# schematic_ap.net
KiCad netlist of a schematic drawn in EAGLE
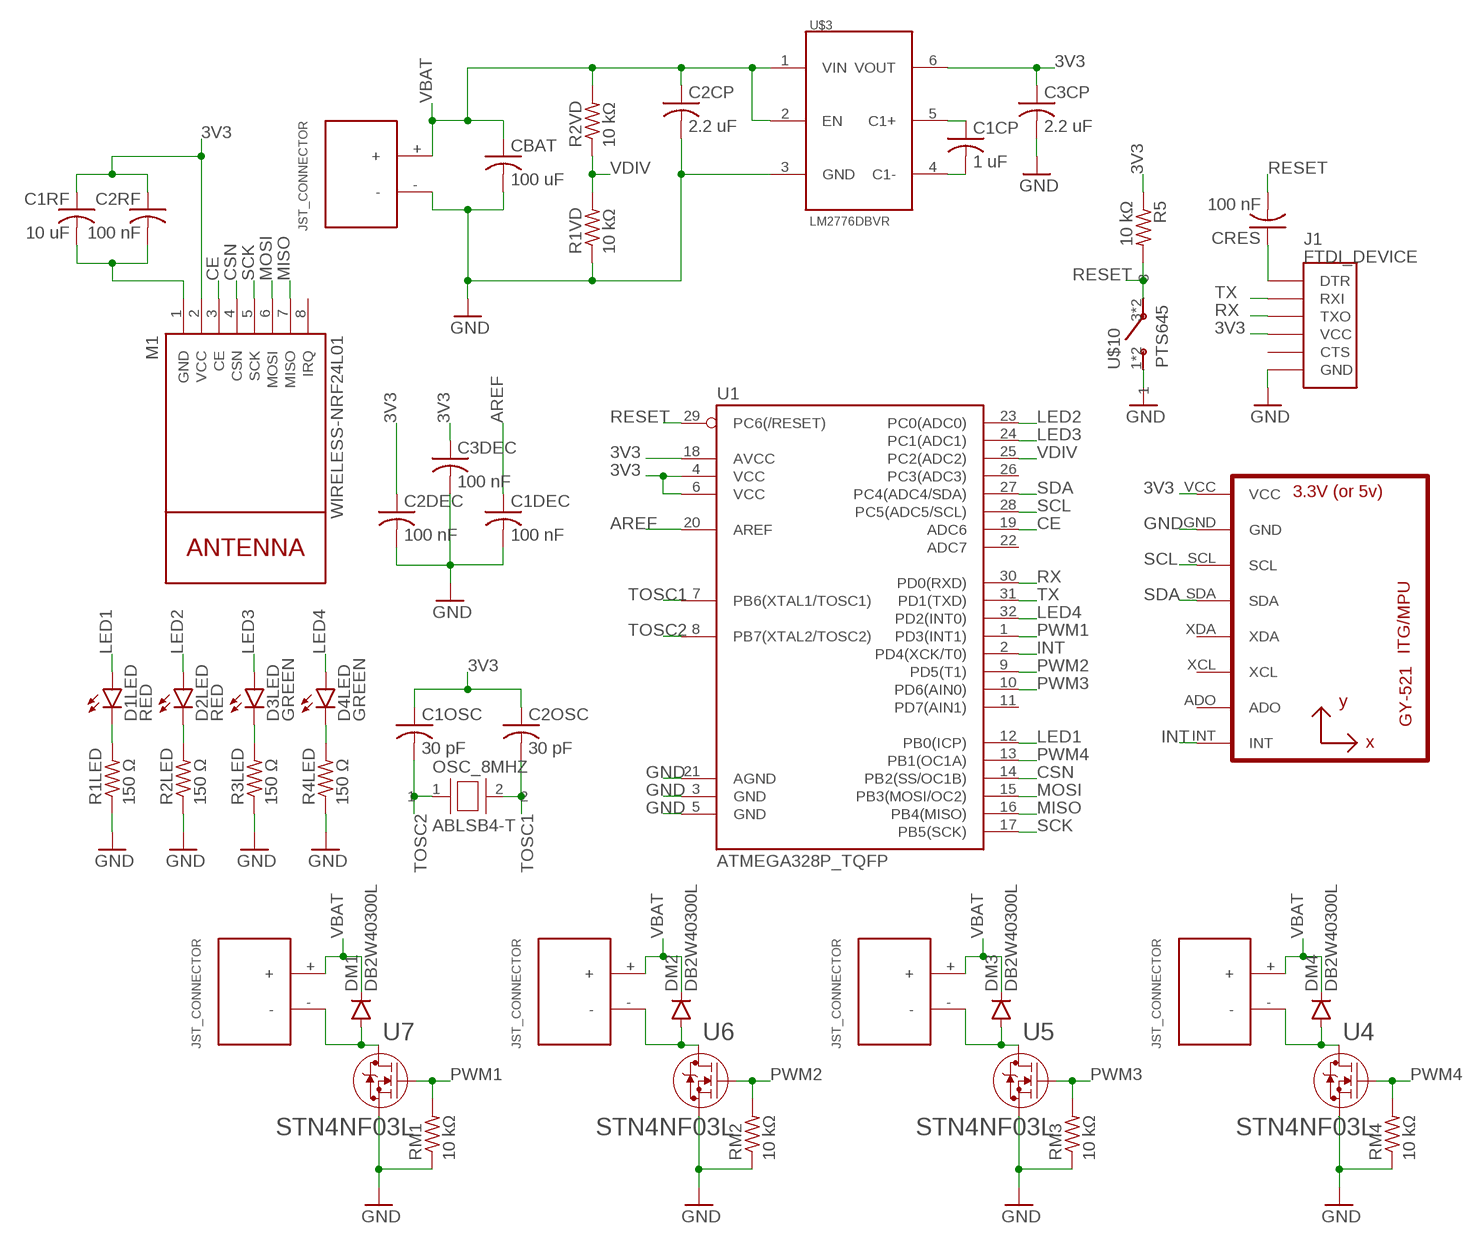
[diagram p0: schematic, sheet 1]

(export (version "E")
  (design (tool "Eeschema 10.0.6"))
  (components
    (comp (ref "C1CP")
      (value "1 uF")
      (footprint "eagle-import:C0603")
      (libsource (lib "eagle-import") (part "C-USC0603"))
    )
    (comp (ref "C1DEC")
      (value "100 nF")
      (footprint "eagle-import:C0603")
      (libsource (lib "eagle-import") (part "C-USC0603"))
    )
    (comp (ref "C1OSC")
      (value "30 pF")
      (footprint "eagle-import:C0603")
      (libsource (lib "eagle-import") (part "C-USC0603"))
    )
    (comp (ref "C1RF")
      (value "10 uF")
      (footprint "eagle-import:C0603")
      (libsource (lib "eagle-import") (part "C-USC0603"))
    )
    (comp (ref "C2CP")
      (value "2.2 uF")
      (footprint "eagle-import:C0603")
      (libsource (lib "eagle-import") (part "C-USC0603"))
    )
    (comp (ref "C2DEC")
      (value "100 nF")
      (footprint "eagle-import:C0603")
      (libsource (lib "eagle-import") (part "C-USC0603"))
    )
    (comp (ref "C2OSC")
      (value "30 pF")
      (footprint "eagle-import:C0603")
      (libsource (lib "eagle-import") (part "C-USC0603"))
    )
    (comp (ref "C2RF")
      (value "100 nF")
      (footprint "eagle-import:C0603")
      (libsource (lib "eagle-import") (part "C-USC0603"))
    )
    (comp (ref "C3CP")
      (value "2.2 uF")
      (footprint "eagle-import:C0603")
      (libsource (lib "eagle-import") (part "C-USC0603"))
    )
    (comp (ref "C3DEC")
      (value "100 nF")
      (footprint "eagle-import:C0603")
      (libsource (lib "eagle-import") (part "C-USC0603"))
    )
    (comp (ref "CBAT")
      (value "100 uF")
      (footprint "eagle-import:C0805")
      (libsource (lib "eagle-import") (part "C-USC0805"))
    )
    (comp (ref "CRES")
      (value "100 nF")
      (footprint "eagle-import:C0603")
      (libsource (lib "eagle-import") (part "C-USC0603"))
    )
    (comp (ref "D1LED")
      (value "RED")
      (footprint "eagle-import:LED-0603")
      (libsource (lib "eagle-import") (part "LED-RED0603"))
    )
    (comp (ref "D2LED")
      (value "RED")
      (footprint "eagle-import:LED-0603")
      (libsource (lib "eagle-import") (part "LED-RED0603"))
    )
    (comp (ref "D3LED")
      (value "GREEN")
      (footprint "eagle-import:LED-0603")
      (libsource (lib "eagle-import") (part "LED-GREEN0603"))
    )
    (comp (ref "D4LED")
      (value "GREEN")
      (footprint "eagle-import:LED-0603")
      (libsource (lib "eagle-import") (part "LED-GREEN0603"))
    )
    (comp (ref "DM1")
      (value "DB2W40300L")
      (footprint "eagle-import:MINI2-F3-B")
      (libsource (lib "eagle-import") (part "DB2W40300L"))
    )
    (comp (ref "DM2")
      (value "DB2W40300L")
      (footprint "eagle-import:MINI2-F3-B")
      (libsource (lib "eagle-import") (part "DB2W40300L"))
    )
    (comp (ref "DM3")
      (value "DB2W40300L")
      (footprint "eagle-import:MINI2-F3-B")
      (libsource (lib "eagle-import") (part "DB2W40300L"))
    )
    (comp (ref "DM4")
      (value "DB2W40300L")
      (footprint "eagle-import:MINI2-F3-B")
      (libsource (lib "eagle-import") (part "DB2W40300L"))
    )
    (comp (ref "J1")
      (value "FTDI_DEVICE")
      (footprint "eagle-import:FTDI_DEVICE_SIDE")
      (libsource (lib "eagle-import") (part "FTDI_DEVICE"))
    )
    (comp (ref "M1")
      (value "WIRELESS-NRF24L01")
      (footprint "eagle-import:WIRELESS-NRF24L01")
      (libsource (lib "eagle-import") (part "WIRELESS-NRF24L01"))
    )
    (comp (ref "OSC_8MHZ")
      (value "ABLSB4-T")
      (footprint "eagle-import:SOT-23")
      (libsource (lib "eagle-import") (part "ABLSB4-T"))
    )
    (comp (ref "R1LED")
      (value "150 Ω")
      (footprint "eagle-import:R0603")
      (libsource (lib "eagle-import") (part "R-US_R0603"))
    )
    (comp (ref "R1VD")
      (value "10 kΩ")
      (footprint "eagle-import:R0603")
      (libsource (lib "eagle-import") (part "R-US_R0603"))
    )
    (comp (ref "R2LED")
      (value "150 Ω")
      (footprint "eagle-import:R0603")
      (libsource (lib "eagle-import") (part "R-US_R0603"))
    )
    (comp (ref "R2VD")
      (value "10 kΩ")
      (footprint "eagle-import:R0603")
      (libsource (lib "eagle-import") (part "R-US_R0603"))
    )
    (comp (ref "R3LED")
      (value "150 Ω")
      (footprint "eagle-import:R0603")
      (libsource (lib "eagle-import") (part "R-US_R0603"))
    )
    (comp (ref "R4LED")
      (value "150 Ω")
      (footprint "eagle-import:R0603")
      (libsource (lib "eagle-import") (part "R-US_R0603"))
    )
    (comp (ref "R5")
      (value "10 kΩ")
      (footprint "eagle-import:R0603")
      (libsource (lib "eagle-import") (part "R-US_R0603"))
    )
    (comp (ref "RM1")
      (value "10 kΩ")
      (footprint "eagle-import:R0603")
      (libsource (lib "eagle-import") (part "R-US_R0603"))
    )
    (comp (ref "RM2")
      (value "10 kΩ")
      (footprint "eagle-import:R0603")
      (libsource (lib "eagle-import") (part "R-US_R0603"))
    )
    (comp (ref "RM3")
      (value "10 kΩ")
      (footprint "eagle-import:R0603")
      (libsource (lib "eagle-import") (part "R-US_R0603"))
    )
    (comp (ref "RM4")
      (value "10 kΩ")
      (footprint "eagle-import:R0603")
      (libsource (lib "eagle-import") (part "R-US_R0603"))
    )
    (comp (ref "U$3")
      (value "LM2776DBVR")
      (footprint "eagle-import:SOT23-5")
      (libsource (lib "eagle-import") (part "LM2776DBVR"))
    )
    (comp (ref "U$4")
      (value "JST_CONNECTOR_FEMALE")
      (footprint "eagle-import:JST_CONNECTOR_FEMALE")
      (libsource (lib "eagle-import") (part "JST_CONNECTOR_FEMALE"))
    )
    (comp (ref "U$5")
      (value "JST_CONNECTOR_FEMALE")
      (footprint "eagle-import:JST_CONNECTOR_FEMALE")
      (libsource (lib "eagle-import") (part "JST_CONNECTOR_FEMALE"))
    )
    (comp (ref "U$7")
      (value "JST_CONNECTOR_FEMALE")
      (footprint "eagle-import:JST_CONNECTOR_FEMALE")
      (libsource (lib "eagle-import") (part "JST_CONNECTOR_FEMALE"))
    )
    (comp (ref "U$9")
      (value "JST_CONNECTOR_FEMALE")
      (footprint "eagle-import:JST_CONNECTOR_FEMALE")
      (libsource (lib "eagle-import") (part "JST_CONNECTOR_FEMALE"))
    )
    (comp (ref "U$10")
      (value "PTS645")
      (footprint "eagle-import:SOT-35")
      (libsource (lib "eagle-import") (part "PTS645"))
    )
    (comp (ref "U$11")
      (value "JST_CONNECTOR_FEMALE")
      (footprint "eagle-import:JST_CONNECTOR_FEMALE")
      (libsource (lib "eagle-import") (part "JST_CONNECTOR_FEMALE"))
    )
    (comp (ref "U1")
      (value "ATMEGA328P_TQFP")
      (footprint "eagle-import:TQFP32-08")
      (libsource (lib "eagle-import") (part "ATMEGA328P_TQFP"))
    )
    (comp (ref "U2")
      (value "GY-521MPU6050")
      (footprint "eagle-import:GY-521")
      (libsource (lib "eagle-import") (part "GY-521MPU6050"))
    )
    (comp (ref "U4")
      (value "STN4NF03L")
      (footprint "eagle-import:SOT-223")
      (libsource (lib "eagle-import") (part "STN4NF03L"))
    )
    (comp (ref "U5")
      (value "STN4NF03L")
      (footprint "eagle-import:SOT-223")
      (libsource (lib "eagle-import") (part "STN4NF03L"))
    )
    (comp (ref "U6")
      (value "STN4NF03L")
      (footprint "eagle-import:SOT-223")
      (libsource (lib "eagle-import") (part "STN4NF03L"))
    )
    (comp (ref "U7")
      (value "STN4NF03L")
      (footprint "eagle-import:SOT-223")
      (libsource (lib "eagle-import") (part "STN4NF03L"))
    )
  )
  (nets
    (net (code "1") (name "/3V3") (class "Default")
      (node (ref "C1OSC") (pin "1") (pinfunction "1_1") (pintype "passive"))
      (node (ref "C1RF") (pin "1") (pinfunction "1_1") (pintype "passive"))
      (node (ref "C2DEC") (pin "1") (pinfunction "1_1") (pintype "passive"))
      (node (ref "C2OSC") (pin "1") (pinfunction "1_1") (pintype "passive"))
      (node (ref "C2RF") (pin "1") (pinfunction "1_1") (pintype "passive"))
      (node (ref "C3CP") (pin "1") (pinfunction "1_1") (pintype "passive"))
      (node (ref "C3DEC") (pin "1") (pinfunction "1_1") (pintype "passive"))
      (node (ref "J1") (pin "P$4") (pinfunction "VCC_P$4") (pintype "bidirectional"))
      (node (ref "M1") (pin "2") (pinfunction "VCC_2") (pintype "power_in"))
      (node (ref "R5") (pin "1") (pinfunction "1_1") (pintype "passive"))
      (node (ref "U$3") (pin "6") (pinfunction "VOUT_6") (pintype "bidirectional"))
      (node (ref "U1") (pin "18") (pinfunction "AVCC_18") (pintype "bidirectional"))
      (node (ref "U1") (pin "4") (pinfunction "VCC_4") (pintype "bidirectional"))
      (node (ref "U1") (pin "6") (pinfunction "VCC_6") (pintype "bidirectional"))
      (node (ref "U2") (pin "VCC") (pinfunction "VCC_VCC") (pintype "bidirectional"))
    )
    (net (code "2") (name "/AREF") (class "Default")
      (node (ref "C1DEC") (pin "1") (pinfunction "1_1") (pintype "passive"))
      (node (ref "U1") (pin "20") (pinfunction "AREF_20") (pintype "bidirectional"))
    )
    (net (code "3") (name "/CE") (class "Default")
      (node (ref "M1") (pin "3") (pinfunction "CE_3") (pintype "bidirectional"))
      (node (ref "U1") (pin "19") (pinfunction "ADC6_19") (pintype "bidirectional"))
    )
    (net (code "4") (name "/CSN") (class "Default")
      (node (ref "M1") (pin "4") (pinfunction "CSN_4") (pintype "bidirectional"))
      (node (ref "U1") (pin "14") (pinfunction "PB2(SS/OC1B)_14") (pintype "bidirectional"))
    )
    (net (code "5") (name "/INT") (class "Default")
      (node (ref "U1") (pin "2") (pinfunction "PD4(XCK/T0)_2") (pintype "bidirectional"))
      (node (ref "U2") (pin "INT") (pinfunction "INT_INT") (pintype "bidirectional"))
    )
    (net (code "6") (name "/LED1") (class "Default")
      (node (ref "D1LED") (pin "A") (pinfunction "A_A") (pintype "passive"))
      (node (ref "U1") (pin "12") (pinfunction "PB0(ICP)_12") (pintype "bidirectional"))
    )
    (net (code "7") (name "/LED2") (class "Default")
      (node (ref "D2LED") (pin "A") (pinfunction "A_A") (pintype "passive"))
      (node (ref "U1") (pin "23") (pinfunction "PC0(ADC0)_23") (pintype "bidirectional"))
    )
    (net (code "8") (name "/LED3") (class "Default")
      (node (ref "D3LED") (pin "A") (pinfunction "A_A") (pintype "passive"))
      (node (ref "U1") (pin "24") (pinfunction "PC1(ADC1)_24") (pintype "bidirectional"))
    )
    (net (code "9") (name "/LED4") (class "Default")
      (node (ref "D4LED") (pin "A") (pinfunction "A_A") (pintype "passive"))
      (node (ref "U1") (pin "32") (pinfunction "PD2(INT0)_32") (pintype "bidirectional"))
    )
    (net (code "10") (name "/MISO") (class "Default")
      (node (ref "M1") (pin "7") (pinfunction "MISO_7") (pintype "bidirectional"))
      (node (ref "U1") (pin "16") (pinfunction "PB4(MISO)_16") (pintype "bidirectional"))
    )
    (net (code "11") (name "/MOSI") (class "Default")
      (node (ref "M1") (pin "6") (pinfunction "MOSI_6") (pintype "bidirectional"))
      (node (ref "U1") (pin "15") (pinfunction "PB3(MOSI/OC2)_15") (pintype "bidirectional"))
    )
    (net (code "12") (name "/PWM1") (class "Default")
      (node (ref "RM1") (pin "2") (pinfunction "2_2") (pintype "passive"))
      (node (ref "U1") (pin "1") (pinfunction "PD3(INT1)_1") (pintype "bidirectional"))
      (node (ref "U7") (pin "1") (pinfunction "1_1") (pintype "passive"))
    )
    (net (code "13") (name "/PWM2") (class "Default")
      (node (ref "RM2") (pin "2") (pinfunction "2_2") (pintype "passive"))
      (node (ref "U1") (pin "9") (pinfunction "PD5(T1)_9") (pintype "bidirectional"))
      (node (ref "U6") (pin "1") (pinfunction "1_1") (pintype "passive"))
    )
    (net (code "14") (name "/PWM3") (class "Default")
      (node (ref "RM3") (pin "2") (pinfunction "2_2") (pintype "passive"))
      (node (ref "U1") (pin "10") (pinfunction "PD6(AIN0)_10") (pintype "bidirectional"))
      (node (ref "U5") (pin "1") (pinfunction "1_1") (pintype "passive"))
    )
    (net (code "15") (name "/PWM4") (class "Default")
      (node (ref "RM4") (pin "2") (pinfunction "2_2") (pintype "passive"))
      (node (ref "U1") (pin "13") (pinfunction "PB1(OC1A)_13") (pintype "bidirectional"))
      (node (ref "U4") (pin "1") (pinfunction "1_1") (pintype "passive"))
    )
    (net (code "16") (name "/RESET") (class "Default")
      (node (ref "CRES") (pin "2") (pinfunction "2_2") (pintype "passive"))
      (node (ref "R5") (pin "2") (pinfunction "2_2") (pintype "passive"))
      (node (ref "U$10") (pin "3") (pinfunction "3_3") (pintype "bidirectional"))
      (node (ref "U$10") (pin "4") (pinfunction "3_4") (pintype "bidirectional"))
      (node (ref "U1") (pin "29") (pinfunction "PC6(/RESET)_29") (pintype "bidirectional"))
    )
    (net (code "17") (name "/RX") (class "Default")
      (node (ref "J1") (pin "P$3") (pinfunction "TXO_P$3") (pintype "bidirectional"))
      (node (ref "U1") (pin "30") (pinfunction "PD0(RXD)_30") (pintype "bidirectional"))
    )
    (net (code "18") (name "/SCK") (class "Default")
      (node (ref "M1") (pin "5") (pinfunction "SCK_5") (pintype "bidirectional"))
      (node (ref "U1") (pin "17") (pinfunction "PB5(SCK)_17") (pintype "bidirectional"))
    )
    (net (code "19") (name "/SCL") (class "Default")
      (node (ref "U1") (pin "28") (pinfunction "PC5(ADC5/SCL)_28") (pintype "bidirectional"))
      (node (ref "U2") (pin "SCL") (pinfunction "SCL_SCL") (pintype "bidirectional"))
    )
    (net (code "20") (name "/SDA") (class "Default")
      (node (ref "U1") (pin "27") (pinfunction "PC4(ADC4/SDA)_27") (pintype "bidirectional"))
      (node (ref "U2") (pin "SDA") (pinfunction "SDA_SDA") (pintype "bidirectional"))
    )
    (net (code "21") (name "/TOSC1") (class "Default")
      (node (ref "C2OSC") (pin "2") (pinfunction "2_2") (pintype "passive"))
      (node (ref "OSC_8MHZ") (pin "2") (pinfunction "2_2") (pintype "bidirectional"))
      (node (ref "U1") (pin "7") (pinfunction "PB6(XTAL1/TOSC1)_7") (pintype "bidirectional"))
    )
    (net (code "22") (name "/TOSC2") (class "Default")
      (node (ref "C1OSC") (pin "2") (pinfunction "2_2") (pintype "passive"))
      (node (ref "OSC_8MHZ") (pin "1") (pinfunction "1_1") (pintype "bidirectional"))
      (node (ref "U1") (pin "8") (pinfunction "PB7(XTAL2/TOSC2)_8") (pintype "bidirectional"))
    )
    (net (code "23") (name "/TX") (class "Default")
      (node (ref "J1") (pin "P$2") (pinfunction "RXI_P$2") (pintype "bidirectional"))
      (node (ref "U1") (pin "31") (pinfunction "PD1(TXD)_31") (pintype "bidirectional"))
    )
    (net (code "24") (name "/VBAT") (class "Default")
      (node (ref "C2CP") (pin "1") (pinfunction "1_1") (pintype "passive"))
      (node (ref "CBAT") (pin "1") (pinfunction "1_1") (pintype "passive"))
      (node (ref "DM1") (pin "NEG") (pinfunction "GPIN_NEG") (pintype "passive"))
      (node (ref "DM2") (pin "NEG") (pinfunction "GPIN_NEG") (pintype "passive"))
      (node (ref "DM3") (pin "NEG") (pinfunction "GPIN_NEG") (pintype "passive"))
      (node (ref "DM4") (pin "NEG") (pinfunction "GPIN_NEG") (pintype "passive"))
      (node (ref "R2VD") (pin "2") (pinfunction "2_2") (pintype "passive"))
      (node (ref "U$11") (pin "+") (pinfunction "+_+") (pintype "bidirectional"))
      (node (ref "U$3") (pin "1") (pinfunction "VIN_1") (pintype "bidirectional"))
      (node (ref "U$3") (pin "2") (pinfunction "EN_2") (pintype "bidirectional"))
      (node (ref "U$4") (pin "+") (pinfunction "+_+") (pintype "bidirectional"))
      (node (ref "U$5") (pin "+") (pinfunction "+_+") (pintype "bidirectional"))
      (node (ref "U$7") (pin "+") (pinfunction "+_+") (pintype "bidirectional"))
      (node (ref "U$9") (pin "+") (pinfunction "+_+") (pintype "bidirectional"))
    )
    (net (code "25") (name "/VDIV") (class "Default")
      (node (ref "R1VD") (pin "2") (pinfunction "2_2") (pintype "passive"))
      (node (ref "R2VD") (pin "1") (pinfunction "1_1") (pintype "passive"))
      (node (ref "U1") (pin "25") (pinfunction "PC2(ADC2)_25") (pintype "bidirectional"))
    )
    (net (code "26") (name "GND") (class "Default")
      (node (ref "C1DEC") (pin "2") (pinfunction "2_2") (pintype "passive"))
      (node (ref "C2CP") (pin "2") (pinfunction "2_2") (pintype "passive"))
      (node (ref "C2DEC") (pin "2") (pinfunction "2_2") (pintype "passive"))
      (node (ref "C3CP") (pin "2") (pinfunction "2_2") (pintype "passive"))
      (node (ref "C3DEC") (pin "2") (pinfunction "2_2") (pintype "passive"))
      (node (ref "CBAT") (pin "2") (pinfunction "2_2") (pintype "passive"))
      (node (ref "J1") (pin "P$6") (pinfunction "GND_P$6") (pintype "bidirectional"))
      (node (ref "R1LED") (pin "1") (pinfunction "1_1") (pintype "passive"))
      (node (ref "R1VD") (pin "1") (pinfunction "1_1") (pintype "passive"))
      (node (ref "R2LED") (pin "1") (pinfunction "1_1") (pintype "passive"))
      (node (ref "R3LED") (pin "1") (pinfunction "1_1") (pintype "passive"))
      (node (ref "R4LED") (pin "1") (pinfunction "1_1") (pintype "passive"))
      (node (ref "RM1") (pin "1") (pinfunction "1_1") (pintype "passive"))
      (node (ref "RM2") (pin "1") (pinfunction "1_1") (pintype "passive"))
      (node (ref "RM3") (pin "1") (pinfunction "1_1") (pintype "passive"))
      (node (ref "RM4") (pin "1") (pinfunction "1_1") (pintype "passive"))
      (node (ref "U$10") (pin "1") (pinfunction "1_1") (pintype "bidirectional"))
      (node (ref "U$10") (pin "2") (pinfunction "1_2") (pintype "bidirectional"))
      (node (ref "U$11") (pin "-") (pinfunction "-_-") (pintype "bidirectional"))
      (node (ref "U$3") (pin "3") (pinfunction "GND_3") (pintype "bidirectional"))
      (node (ref "U1") (pin "21") (pinfunction "AGND_21") (pintype "bidirectional"))
      (node (ref "U1") (pin "3") (pinfunction "GND_3") (pintype "bidirectional"))
      (node (ref "U1") (pin "5") (pinfunction "GND_5") (pintype "bidirectional"))
      (node (ref "U2") (pin "GND") (pinfunction "GND_GND") (pintype "bidirectional"))
      (node (ref "U4") (pin "3") (pinfunction "3_3") (pintype "passive"))
      (node (ref "U5") (pin "3") (pinfunction "3_3") (pintype "passive"))
      (node (ref "U6") (pin "3") (pinfunction "3_3") (pintype "passive"))
      (node (ref "U7") (pin "3") (pinfunction "3_3") (pintype "passive"))
    )
    (net (code "27") (name "Net-(D1LED-PadC)") (class "Default")
      (node (ref "D1LED") (pin "C") (pinfunction "C_C") (pintype "passive"))
      (node (ref "R1LED") (pin "2") (pinfunction "2_2") (pintype "passive"))
    )
    (net (code "28") (name "Net-(D2LED-PadC)") (class "Default")
      (node (ref "D2LED") (pin "C") (pinfunction "C_C") (pintype "passive"))
      (node (ref "R2LED") (pin "2") (pinfunction "2_2") (pintype "passive"))
    )
    (net (code "29") (name "Net-(D3LED-PadC)") (class "Default")
      (node (ref "D3LED") (pin "C") (pinfunction "C_C") (pintype "passive"))
      (node (ref "R3LED") (pin "2") (pinfunction "2_2") (pintype "passive"))
    )
    (net (code "30") (name "Net-(D4LED-PadC)") (class "Default")
      (node (ref "D4LED") (pin "C") (pinfunction "C_C") (pintype "passive"))
      (node (ref "R4LED") (pin "2") (pinfunction "2_2") (pintype "passive"))
    )
    (net (code "31") (name "Net-(DM1-PPIN)") (class "Default")
      (node (ref "DM1") (pin "POS") (pinfunction "PPIN_POS") (pintype "passive"))
      (node (ref "U$4") (pin "-") (pinfunction "-_-") (pintype "bidirectional"))
      (node (ref "U7") (pin "2") (pinfunction "2_2") (pintype "passive"))
    )
    (net (code "32") (name "Net-(DM2-PPIN)") (class "Default")
      (node (ref "DM2") (pin "POS") (pinfunction "PPIN_POS") (pintype "passive"))
      (node (ref "U$5") (pin "-") (pinfunction "-_-") (pintype "bidirectional"))
      (node (ref "U6") (pin "2") (pinfunction "2_2") (pintype "passive"))
    )
    (net (code "33") (name "Net-(DM3-PPIN)") (class "Default")
      (node (ref "DM3") (pin "POS") (pinfunction "PPIN_POS") (pintype "passive"))
      (node (ref "U$7") (pin "-") (pinfunction "-_-") (pintype "bidirectional"))
      (node (ref "U5") (pin "2") (pinfunction "2_2") (pintype "passive"))
    )
    (net (code "34") (name "Net-(DM4-PPIN)") (class "Default")
      (node (ref "DM4") (pin "POS") (pinfunction "PPIN_POS") (pintype "passive"))
      (node (ref "U$9") (pin "-") (pinfunction "-_-") (pintype "bidirectional"))
      (node (ref "U4") (pin "2") (pinfunction "2_2") (pintype "passive"))
    )
    (net (code "35") (name "Net-(J1-DTR)") (class "Default")
      (node (ref "CRES") (pin "1") (pinfunction "1_1") (pintype "passive"))
      (node (ref "J1") (pin "P$1") (pinfunction "DTR_P$1") (pintype "bidirectional"))
    )
    (net (code "36") (name "Net-(M1-GND)") (class "Default")
      (node (ref "C1RF") (pin "2") (pinfunction "2_2") (pintype "passive"))
      (node (ref "C2RF") (pin "2") (pinfunction "2_2") (pintype "passive"))
      (node (ref "M1") (pin "1") (pinfunction "GND_1") (pintype "power_in"))
    )
    (net (code "37") (name "Net-(U$3-C1+)") (class "Default")
      (node (ref "C1CP") (pin "1") (pinfunction "1_1") (pintype "passive"))
      (node (ref "U$3") (pin "5") (pinfunction "C1+_5") (pintype "bidirectional"))
    )
    (net (code "38") (name "Net-(U$3-C1-)") (class "Default")
      (node (ref "C1CP") (pin "2") (pinfunction "2_2") (pintype "passive"))
      (node (ref "U$3") (pin "4") (pinfunction "C1-_4") (pintype "bidirectional"))
    )
    (net (code "39") (name "unconnected-(J1-CTS-PadP$5)") (class "Default")
      (node (ref "J1") (pin "P$5") (pinfunction "CTS_P$5") (pintype "bidirectional"))
    )
    (net (code "40") (name "unconnected-(M1-IRQ-Pad8)") (class "Default")
      (node (ref "M1") (pin "8") (pinfunction "IRQ_8") (pintype "bidirectional"))
    )
    (net (code "41") (name "unconnected-(U1-ADC7-Pad22)") (class "Default")
      (node (ref "U1") (pin "22") (pinfunction "ADC7_22") (pintype "bidirectional"))
    )
    (net (code "42") (name "unconnected-(U1-PC3(ADC3)-Pad26)") (class "Default")
      (node (ref "U1") (pin "26") (pinfunction "PC3(ADC3)_26") (pintype "bidirectional"))
    )
    (net (code "43") (name "unconnected-(U1-PD7(AIN1)-Pad11)") (class "Default")
      (node (ref "U1") (pin "11") (pinfunction "PD7(AIN1)_11") (pintype "bidirectional"))
    )
    (net (code "44") (name "unconnected-(U2-PadADO)") (class "Default")
      (node (ref "U2") (pin "ADO") (pinfunction "ADO_ADO") (pintype "bidirectional"))
    )
    (net (code "45") (name "unconnected-(U2-PadXCL)") (class "Default")
      (node (ref "U2") (pin "XCL") (pinfunction "XCL_XCL") (pintype "bidirectional"))
    )
    (net (code "46") (name "unconnected-(U2-PadXDA)") (class "Default")
      (node (ref "U2") (pin "XDA") (pinfunction "XDA_XDA") (pintype "bidirectional"))
    )
  )
)
